# external_ps_en.net
KiCad netlist of a schematic drawn in Altium Designer
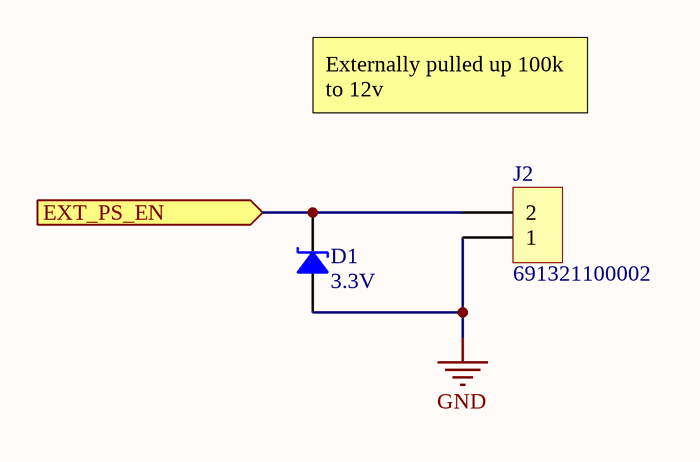
[diagram p0: external_ps_en.SchDoc]

(export (version "E")
  (design (tool "Eeschema 10.0.6"))
  (components
    (comp (ref "D1")
      (value "3.3V")
      (footprint "SOD123F")
      (description "Zener Diode")
      (libsource (lib "Diodes") (part "Diode Zener"))
    )
    (comp (ref "J2")
      (value "691321100002")
      (footprint "691322110002")
      (description "WR-TBL Terminal block - serie 3211 - 3.50 mm")
      (fields
        (field (name "MANUFACTURER") "Würth Elektronik eiSos GmbH")
        (field (name "CREATED BY") "Karrer Zheng")
      )
      (libsource (lib "ALTIUM-TBL_3_50_3211_VERTICAL_PCB_HEADER_69132110000X-rev15c") (part "691321100002"))
    )
  )
  (nets
    (net (code "1") (name "/EXT_PS_EN") (class "Default")
      (node (ref "D1") (pin "2") (pinfunction "2_2") (pintype "passive"))
      (node (ref "J2") (pin "2") (pinfunction "2_2") (pintype "passive"))
    )
    (net (code "2") (name "GND") (class "Default")
      (node (ref "D1") (pin "1") (pinfunction "1_1") (pintype "passive"))
      (node (ref "J2") (pin "1") (pinfunction "1_1") (pintype "passive"))
    )
  )
)
